# EncLickDrv_J0104132C-ESPrevB.net
KiCad netlist of a schematic drawn in EAGLE
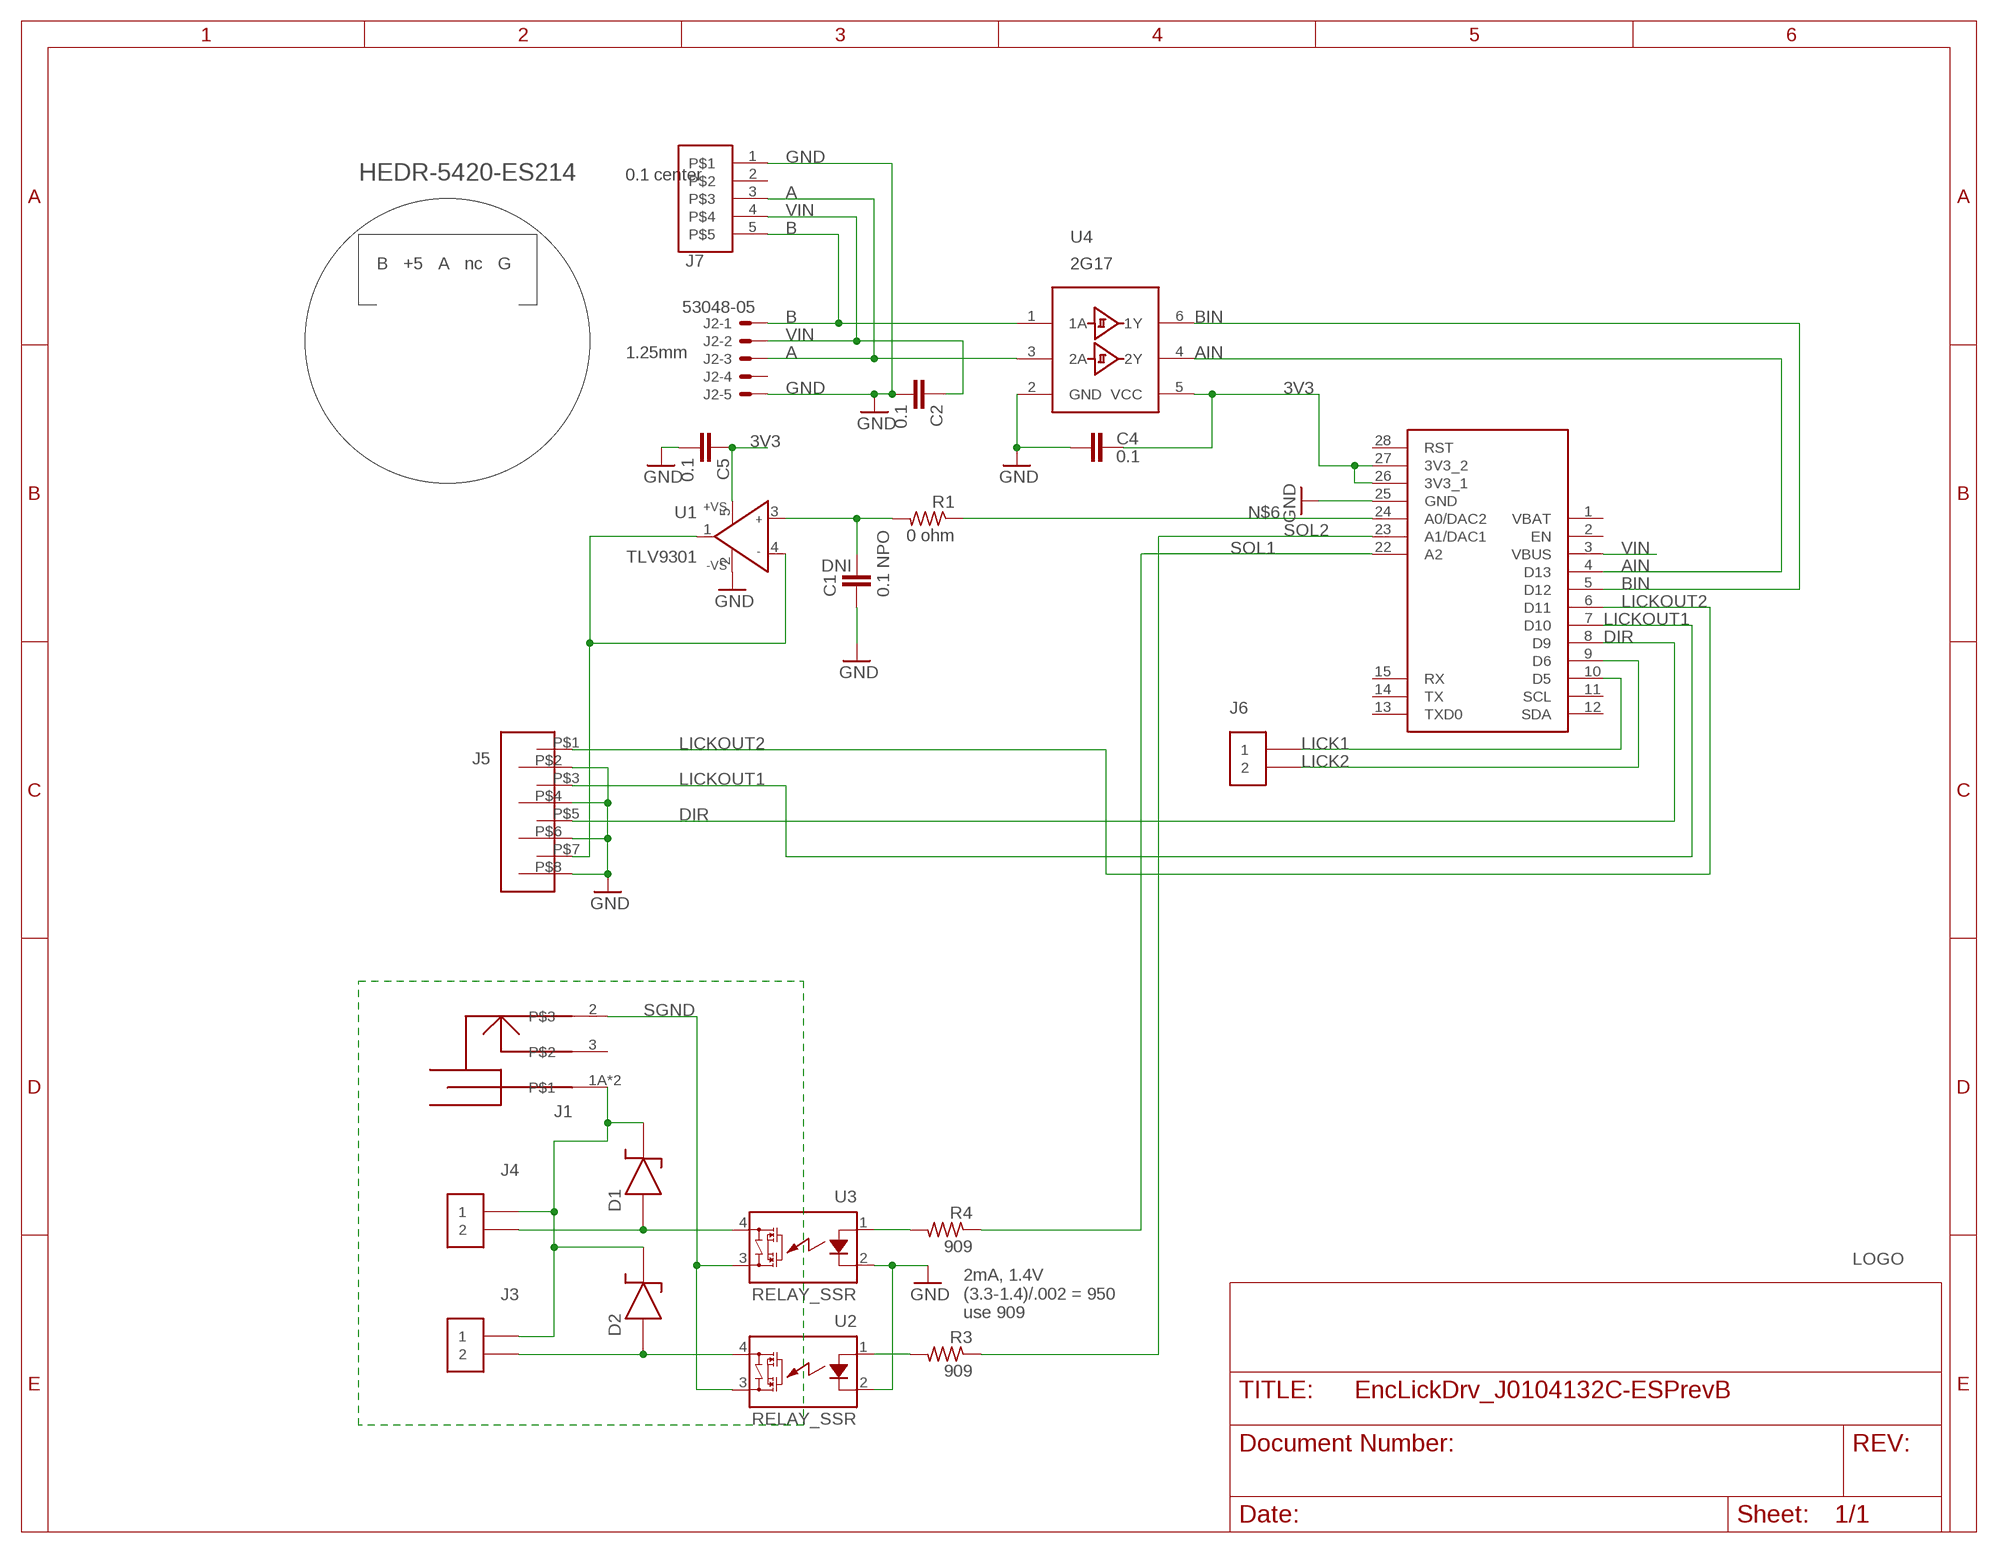
[diagram p0: schematic, sheet 1]

(export (version "E")
  (design (tool "Eeschema 10.0.6"))
  (components
    (comp (ref "C1")
      (value "0.1 NPO")
      (footprint "eagle-import:1206S")
      (libsource (lib "eagle-import") (part "CAPS1206S"))
    )
    (comp (ref "C2")
      (value "0.1")
      (footprint "eagle-import:0603S")
      (libsource (lib "eagle-import") (part "CAPS0603S"))
    )
    (comp (ref "C4")
      (value "0.1")
      (footprint "eagle-import:0603S")
      (libsource (lib "eagle-import") (part "CAPS0603S"))
    )
    (comp (ref "C5")
      (value "0.1")
      (footprint "eagle-import:0603S")
      (libsource (lib "eagle-import") (part "CAPS0603S"))
    )
    (comp (ref "D1")
      (value "DIODE_SCHOTTKYPWRDI-123")
      (footprint "eagle-import:PWRDI-123")
      (libsource (lib "eagle-import") (part "DIODE_SCHOTTKYPWRDI-123"))
    )
    (comp (ref "D2")
      (value "DIODE_SCHOTTKYPWRDI-123")
      (footprint "eagle-import:PWRDI-123")
      (libsource (lib "eagle-import") (part "DIODE_SCHOTTKYPWRDI-123"))
    )
    (comp (ref "J1")
      (value "POWER_JACK_SHUNTPJ-002")
      (footprint "eagle-import:PJ-002")
      (libsource (lib "eagle-import") (part "POWER_JACK_SHUNTPJ-002"))
    )
    (comp (ref "J2")
      (value "53048-05")
      (footprint "eagle-import:53048-05")
      (fields (field (name "MF") "MOLEX") (field (name "MPN") "53048-0510"))
      (libsource (lib "eagle-import") (part "53?-05048"))
    )
    (comp (ref "J3")
      (value "CON21881558")
      (footprint "eagle-import:1881558")
      (libsource (lib "eagle-import") (part "CON21881558"))
    )
    (comp (ref "J4")
      (value "CON21881558")
      (footprint "eagle-import:1881558")
      (libsource (lib "eagle-import") (part "CON21881558"))
    )
    (comp (ref "J5")
      (value "CON81844743")
      (footprint "eagle-import:1844743")
      (libsource (lib "eagle-import") (part "CON81844743"))
    )
    (comp (ref "J6")
      (value "CON21881558")
      (footprint "eagle-import:1881558")
      (libsource (lib "eagle-import") (part "CON21881558"))
    )
    (comp (ref "J7")
      (value "CON5104361-4")
      (footprint "eagle-import:104361-4")
      (libsource (lib "eagle-import") (part "CON5104361-4"))
    )
    (comp (ref "M1")
      (value "ESP32=S2-REV-TFT-NO16-21")
      (footprint "eagle-import:ESP32-S2-REV-TFT-NO16-21")
      (libsource (lib "eagle-import") (part "ESP32=S2-REV-TFT-NO16-21"))
    )
    (comp (ref "R1")
      (value "0 ohm")
      (footprint "eagle-import:0805S")
      (libsource (lib "eagle-import") (part "RESISTOR_SM0805S"))
    )
    (comp (ref "R3")
      (value "909")
      (footprint "eagle-import:0805S")
      (libsource (lib "eagle-import") (part "RESISTOR_SM0805S"))
    )
    (comp (ref "R4")
      (value "909")
      (footprint "eagle-import:0805S")
      (libsource (lib "eagle-import") (part "RESISTOR_SM0805S"))
    )
    (comp (ref "U$1")
      (value "JFRC-LOGOLOGO_OP")
      (footprint "eagle-import:LOGO_BMP_OP")
      (libsource (lib "eagle-import") (part "JFRC-LOGOLOGO_OP"))
    )
    (comp (ref "U1")
      (value "TLV9301")
      (footprint "eagle-import:SOT23-5")
      (fields (field (name "MF") "ALTERA CORPORATION") (field (name "MPN") "AD8065ARTZ-REEL7"))
      (libsource (lib "eagle-import") (part "AD8065RT"))
    )
    (comp (ref "U2")
      (value "RELAY_SSR")
      (footprint "eagle-import:SSR_SOIP")
      (libsource (lib "eagle-import") (part "RELAY_SSR"))
    )
    (comp (ref "U3")
      (value "RELAY_SSR")
      (footprint "eagle-import:SSR_SOIP")
      (libsource (lib "eagle-import") (part "RELAY_SSR"))
    )
    (comp (ref "U4")
      (value "2G17")
      (footprint "eagle-import:SOT23-6")
      (libsource (lib "eagle-import") (part "2G17"))
    )
  )
  (nets
    (net (code "1") (name "/3V3") (class "Default")
      (node (ref "C4") (pin "1") (pinfunction "1_1") (pintype "passive"))
      (node (ref "C5") (pin "1") (pinfunction "1_1") (pintype "passive"))
      (node (ref "M1") (pin "26") (pinfunction "3V3_1_26") (pintype "bidirectional"))
      (node (ref "M1") (pin "27") (pinfunction "3V3_2_27") (pintype "bidirectional"))
      (node (ref "U1") (pin "5") (pinfunction "+VS_5") (pintype "input"))
      (node (ref "U4") (pin "5") (pinfunction "VCC_5") (pintype "bidirectional"))
    )
    (net (code "2") (name "/A") (class "Default")
      (node (ref "J2") (pin "3") (pinfunction "S_3") (pintype "passive"))
      (node (ref "J7") (pin "3") (pinfunction "P$3_3") (pintype "bidirectional"))
      (node (ref "U4") (pin "3") (pinfunction "2A_3") (pintype "bidirectional"))
    )
    (net (code "3") (name "/AIN") (class "Default")
      (node (ref "M1") (pin "4") (pinfunction "D13_4") (pintype "bidirectional"))
      (node (ref "U4") (pin "4") (pinfunction "2Y_4") (pintype "bidirectional"))
    )
    (net (code "4") (name "/B") (class "Default")
      (node (ref "J2") (pin "1") (pinfunction "S_1") (pintype "passive"))
      (node (ref "J7") (pin "5") (pinfunction "P$5_5") (pintype "bidirectional"))
      (node (ref "U4") (pin "1") (pinfunction "1A_1") (pintype "bidirectional"))
    )
    (net (code "5") (name "/BIN") (class "Default")
      (node (ref "M1") (pin "5") (pinfunction "D12_5") (pintype "bidirectional"))
      (node (ref "U4") (pin "6") (pinfunction "1Y_6") (pintype "bidirectional"))
    )
    (net (code "6") (name "/DIR") (class "Default")
      (node (ref "J5") (pin "P$5") (pinfunction "5_P$5") (pintype "bidirectional"))
      (node (ref "M1") (pin "8") (pinfunction "D9_8") (pintype "bidirectional"))
    )
    (net (code "7") (name "/LICK1") (class "Default")
      (node (ref "J6") (pin "1") (pinfunction "1_1") (pintype "bidirectional"))
      (node (ref "M1") (pin "10") (pinfunction "D5_10") (pintype "bidirectional"))
    )
    (net (code "8") (name "/LICK2") (class "Default")
      (node (ref "J6") (pin "2") (pinfunction "2_2") (pintype "bidirectional"))
      (node (ref "M1") (pin "9") (pinfunction "D6_9") (pintype "bidirectional"))
    )
    (net (code "9") (name "/LICKOUT1") (class "Default")
      (node (ref "J5") (pin "P$3") (pinfunction "3_P$3") (pintype "bidirectional"))
      (node (ref "M1") (pin "7") (pinfunction "D10_7") (pintype "bidirectional"))
    )
    (net (code "10") (name "/LICKOUT2") (class "Default")
      (node (ref "J5") (pin "P$1") (pinfunction "1_P$1") (pintype "bidirectional"))
      (node (ref "M1") (pin "6") (pinfunction "D11_6") (pintype "bidirectional"))
    )
    (net (code "11") (name "/N$6") (class "Default")
      (node (ref "M1") (pin "24") (pinfunction "A0/DAC2_24") (pintype "bidirectional"))
      (node (ref "R1") (pin "1") (pinfunction "1_1") (pintype "passive"))
    )
    (net (code "12") (name "/SGND") (class "Default")
      (node (ref "J1") (pin "2") (pinfunction "P$3_2") (pintype "bidirectional"))
      (node (ref "U2") (pin "3") (pinfunction "DS2_3") (pintype "passive"))
      (node (ref "U3") (pin "3") (pinfunction "DS2_3") (pintype "passive"))
    )
    (net (code "13") (name "/SOL1") (class "Default")
      (node (ref "M1") (pin "22") (pinfunction "A2_22") (pintype "bidirectional"))
      (node (ref "R4") (pin "1") (pinfunction "1_1") (pintype "passive"))
    )
    (net (code "14") (name "/SOL2") (class "Default")
      (node (ref "M1") (pin "23") (pinfunction "A1/DAC1_23") (pintype "bidirectional"))
      (node (ref "R3") (pin "1") (pinfunction "1_1") (pintype "passive"))
    )
    (net (code "15") (name "/VIN") (class "Default")
      (node (ref "C2") (pin "1") (pinfunction "1_1") (pintype "passive"))
      (node (ref "J2") (pin "2") (pinfunction "S_2") (pintype "passive"))
      (node (ref "J7") (pin "4") (pinfunction "P$4_4") (pintype "bidirectional"))
      (node (ref "M1") (pin "3") (pinfunction "VBUS_3") (pintype "bidirectional"))
    )
    (net (code "16") (name "GND") (class "Default")
      (node (ref "C1") (pin "2") (pinfunction "2_2") (pintype "passive"))
      (node (ref "C2") (pin "2") (pinfunction "2_2") (pintype "passive"))
      (node (ref "C4") (pin "2") (pinfunction "2_2") (pintype "passive"))
      (node (ref "C5") (pin "2") (pinfunction "2_2") (pintype "passive"))
      (node (ref "J2") (pin "5") (pinfunction "S_5") (pintype "passive"))
      (node (ref "J5") (pin "P$2") (pinfunction "2_P$2") (pintype "bidirectional"))
      (node (ref "J5") (pin "P$4") (pinfunction "4_P$4") (pintype "bidirectional"))
      (node (ref "J5") (pin "P$6") (pinfunction "6_P$6") (pintype "bidirectional"))
      (node (ref "J5") (pin "P$8") (pinfunction "8_P$8") (pintype "bidirectional"))
      (node (ref "J7") (pin "1") (pinfunction "P$1_1") (pintype "bidirectional"))
      (node (ref "M1") (pin "25") (pinfunction "GND_25") (pintype "bidirectional"))
      (node (ref "U1") (pin "2") (pinfunction "-VS_2") (pintype "input"))
      (node (ref "U2") (pin "2") (pinfunction "K_2") (pintype "passive"))
      (node (ref "U3") (pin "2") (pinfunction "K_2") (pintype "passive"))
      (node (ref "U4") (pin "2") (pinfunction "GND_2") (pintype "bidirectional"))
    )
    (net (code "17") (name "Net-(D1-PadK)") (class "Default")
      (node (ref "D1") (pin "K") (pinfunction "K_K") (pintype "bidirectional"))
      (node (ref "D2") (pin "K") (pinfunction "K_K") (pintype "bidirectional"))
      (node (ref "J1") (pin "1A") (pinfunction "P$1_1A") (pintype "bidirectional"))
      (node (ref "J1") (pin "1B") (pinfunction "P$1_1B") (pintype "bidirectional"))
      (node (ref "J3") (pin "1") (pinfunction "1_1") (pintype "bidirectional"))
      (node (ref "J4") (pin "1") (pinfunction "1_1") (pintype "bidirectional"))
    )
    (net (code "18") (name "Net-(J5-7)") (class "Default")
      (node (ref "J5") (pin "P$7") (pinfunction "7_P$7") (pintype "bidirectional"))
      (node (ref "U1") (pin "1") (pinfunction "OUT_1") (pintype "output"))
      (node (ref "U1") (pin "4") (pinfunction "IN-_4") (pintype "input"))
    )
    (net (code "19") (name "Net-(U1-IN+)") (class "Default")
      (node (ref "C1") (pin "1") (pinfunction "1_1") (pintype "passive"))
      (node (ref "R1") (pin "2") (pinfunction "2_2") (pintype "passive"))
      (node (ref "U1") (pin "3") (pinfunction "IN+_3") (pintype "input"))
    )
    (net (code "20") (name "Net-(U2-A)") (class "Default")
      (node (ref "R3") (pin "2") (pinfunction "2_2") (pintype "passive"))
      (node (ref "U2") (pin "1") (pinfunction "A_1") (pintype "passive"))
    )
    (net (code "21") (name "Net-(U2-DS1)") (class "Default")
      (node (ref "D2") (pin "A") (pinfunction "A_A") (pintype "bidirectional"))
      (node (ref "J3") (pin "2") (pinfunction "2_2") (pintype "bidirectional"))
      (node (ref "U2") (pin "4") (pinfunction "DS1_4") (pintype "passive"))
    )
    (net (code "22") (name "Net-(U3-A)") (class "Default")
      (node (ref "R4") (pin "2") (pinfunction "2_2") (pintype "passive"))
      (node (ref "U3") (pin "1") (pinfunction "A_1") (pintype "passive"))
    )
    (net (code "23") (name "Net-(U3-DS1)") (class "Default")
      (node (ref "D1") (pin "A") (pinfunction "A_A") (pintype "bidirectional"))
      (node (ref "J4") (pin "2") (pinfunction "2_2") (pintype "bidirectional"))
      (node (ref "U3") (pin "4") (pinfunction "DS1_4") (pintype "passive"))
    )
    (net (code "24") (name "unconnected-(J1-P$2-Pad3)") (class "Default")
      (node (ref "J1") (pin "3") (pinfunction "P$2_3") (pintype "bidirectional"))
    )
    (net (code "25") (name "unconnected-(J2D-S-Pad4)") (class "Default")
      (node (ref "J2") (pin "4") (pinfunction "S_4") (pintype "passive"))
    )
    (net (code "26") (name "unconnected-(J7-P$2-Pad2)") (class "Default")
      (node (ref "J7") (pin "2") (pinfunction "P$2_2") (pintype "bidirectional"))
    )
    (net (code "27") (name "unconnected-(M1-EN-Pad2)") (class "Default")
      (node (ref "M1") (pin "2") (pinfunction "EN_2") (pintype "bidirectional"))
    )
    (net (code "28") (name "unconnected-(M1-RST-Pad28)") (class "Default")
      (node (ref "M1") (pin "28") (pinfunction "RST_28") (pintype "bidirectional"))
    )
    (net (code "29") (name "unconnected-(M1-RX-Pad15)") (class "Default")
      (node (ref "M1") (pin "15") (pinfunction "RX_15") (pintype "bidirectional"))
    )
    (net (code "30") (name "unconnected-(M1-SCL-Pad11)") (class "Default")
      (node (ref "M1") (pin "11") (pinfunction "SCL_11") (pintype "bidirectional"))
    )
    (net (code "31") (name "unconnected-(M1-SDA-Pad12)") (class "Default")
      (node (ref "M1") (pin "12") (pinfunction "SDA_12") (pintype "bidirectional"))
    )
    (net (code "32") (name "unconnected-(M1-TX-Pad14)") (class "Default")
      (node (ref "M1") (pin "14") (pinfunction "TX_14") (pintype "bidirectional"))
    )
    (net (code "33") (name "unconnected-(M1-TXD0-Pad13)") (class "Default")
      (node (ref "M1") (pin "13") (pinfunction "TXD0_13") (pintype "bidirectional"))
    )
    (net (code "34") (name "unconnected-(M1-VBAT-Pad1)") (class "Default")
      (node (ref "M1") (pin "1") (pinfunction "VBAT_1") (pintype "bidirectional"))
    )
  )
)
